# CRD.net
KiCad netlist of a schematic drawn in EAGLE
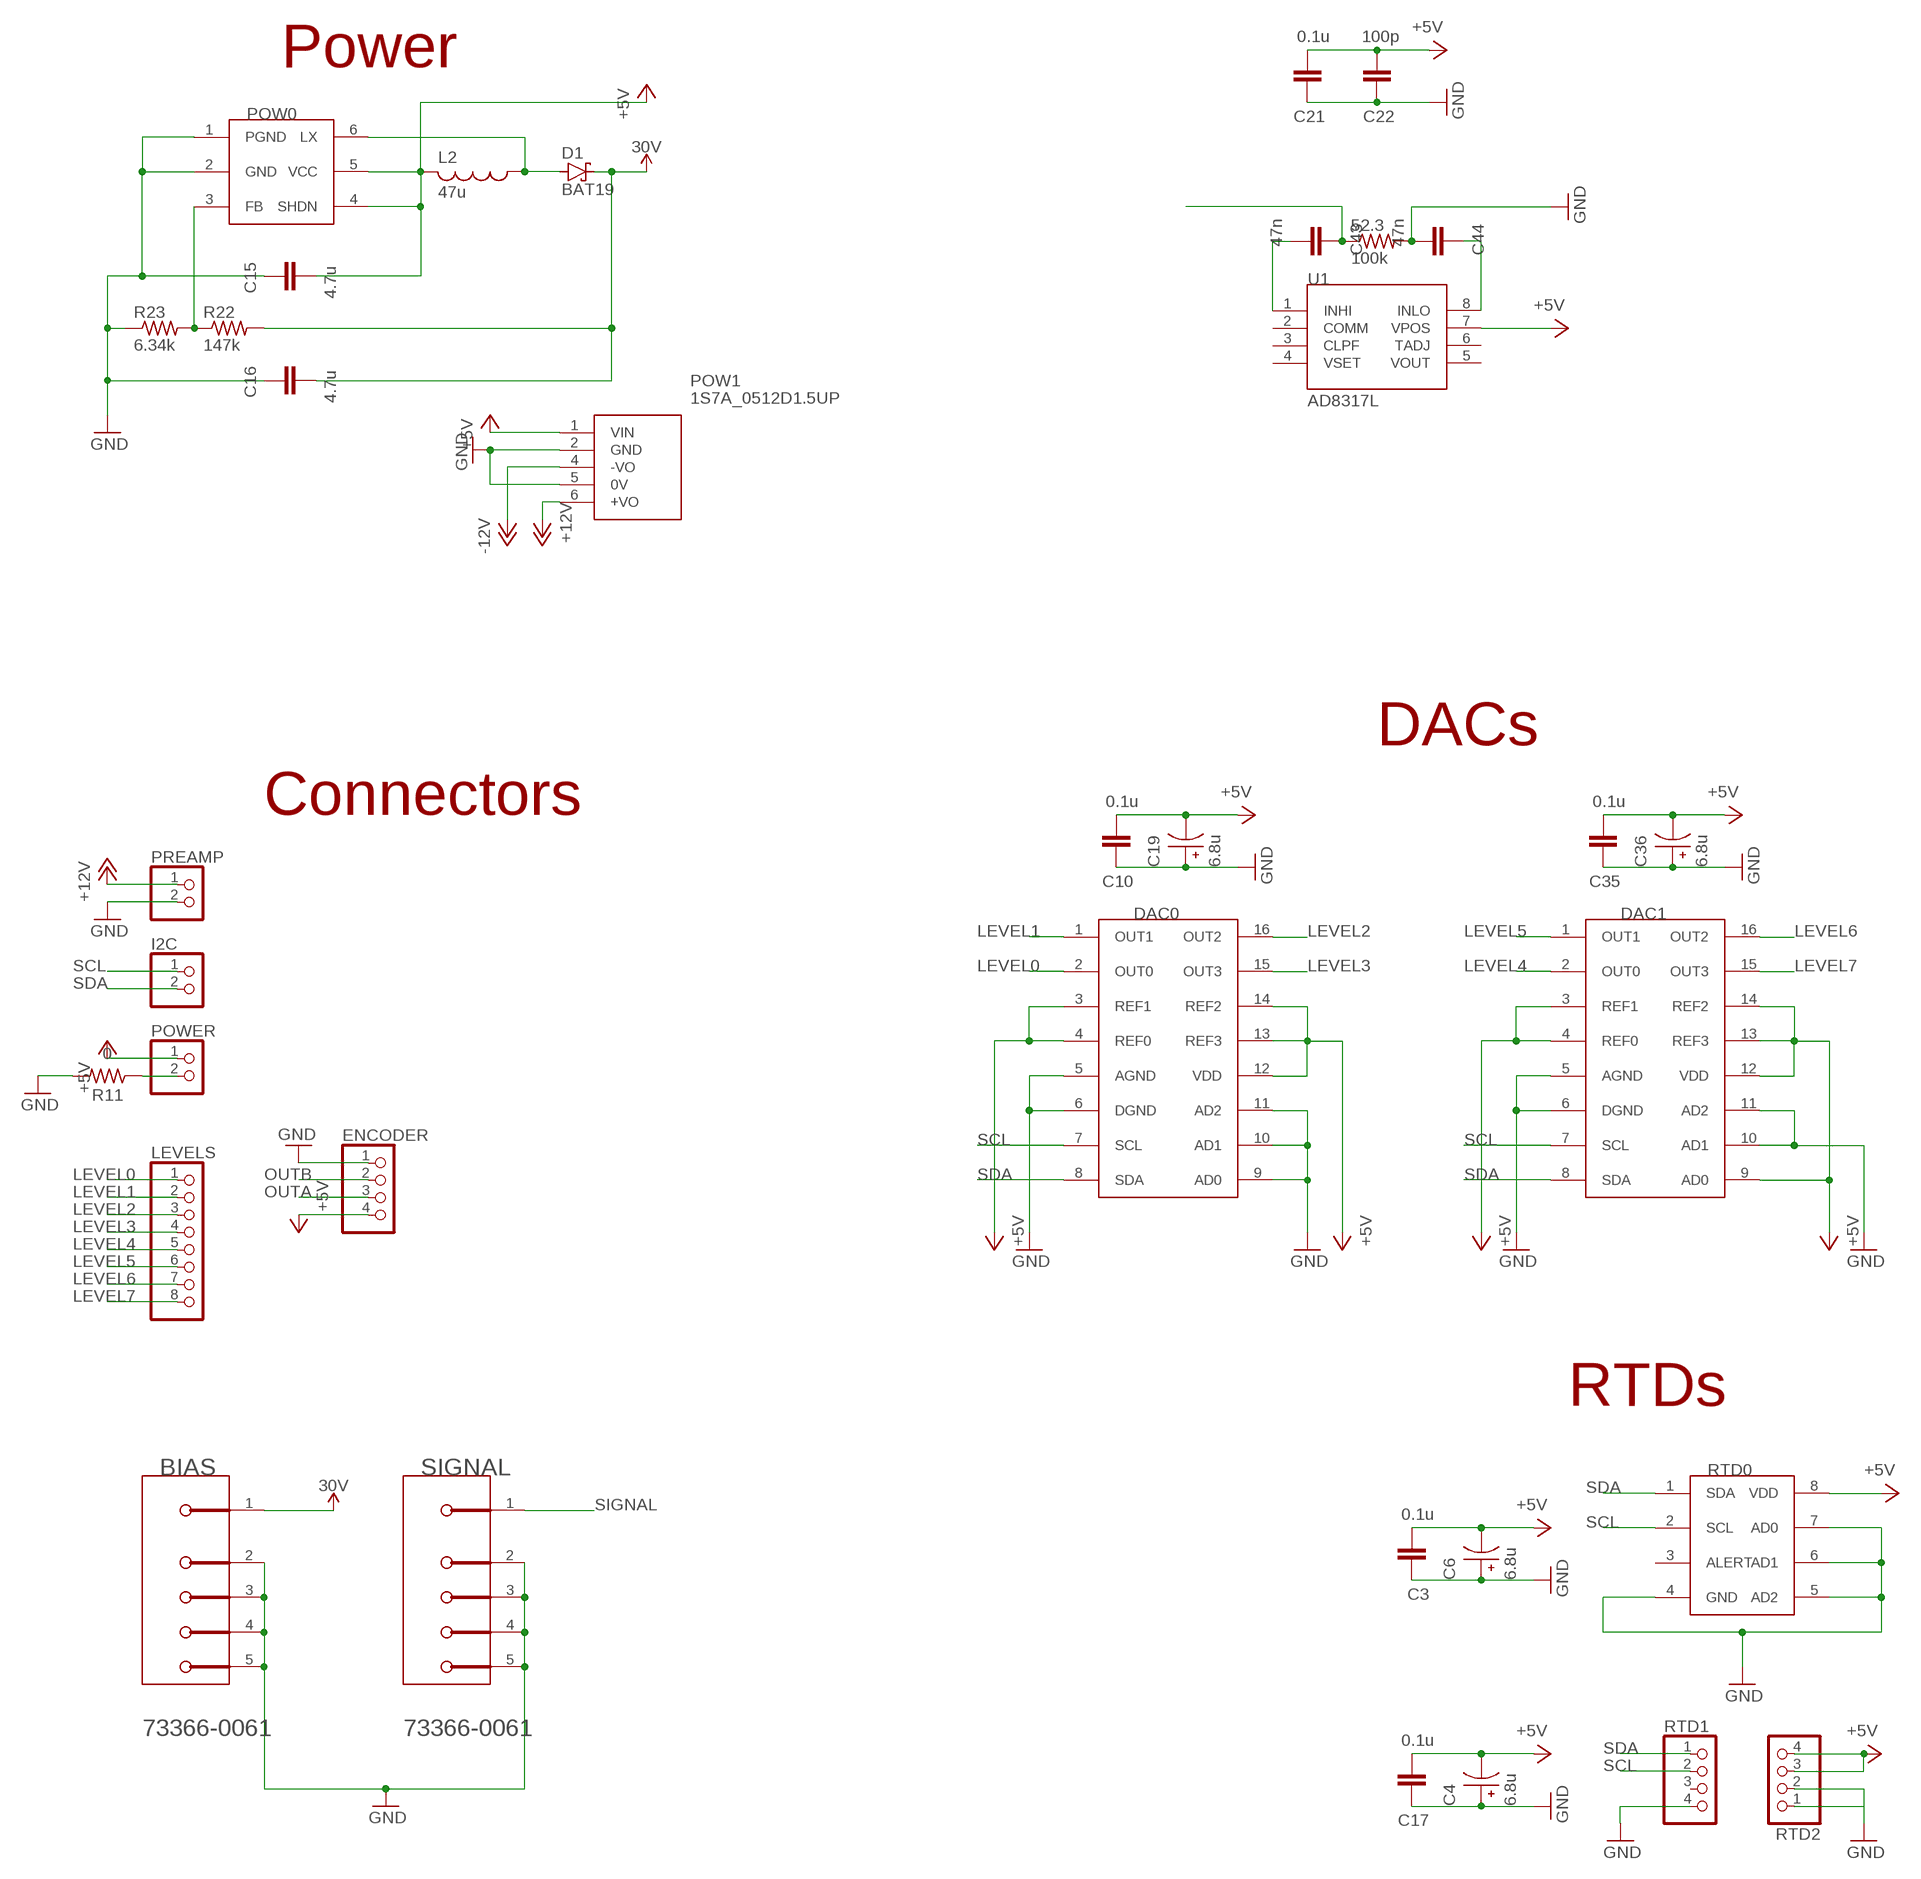
[diagram p0: schematic, sheet 1, part 1 of 2]
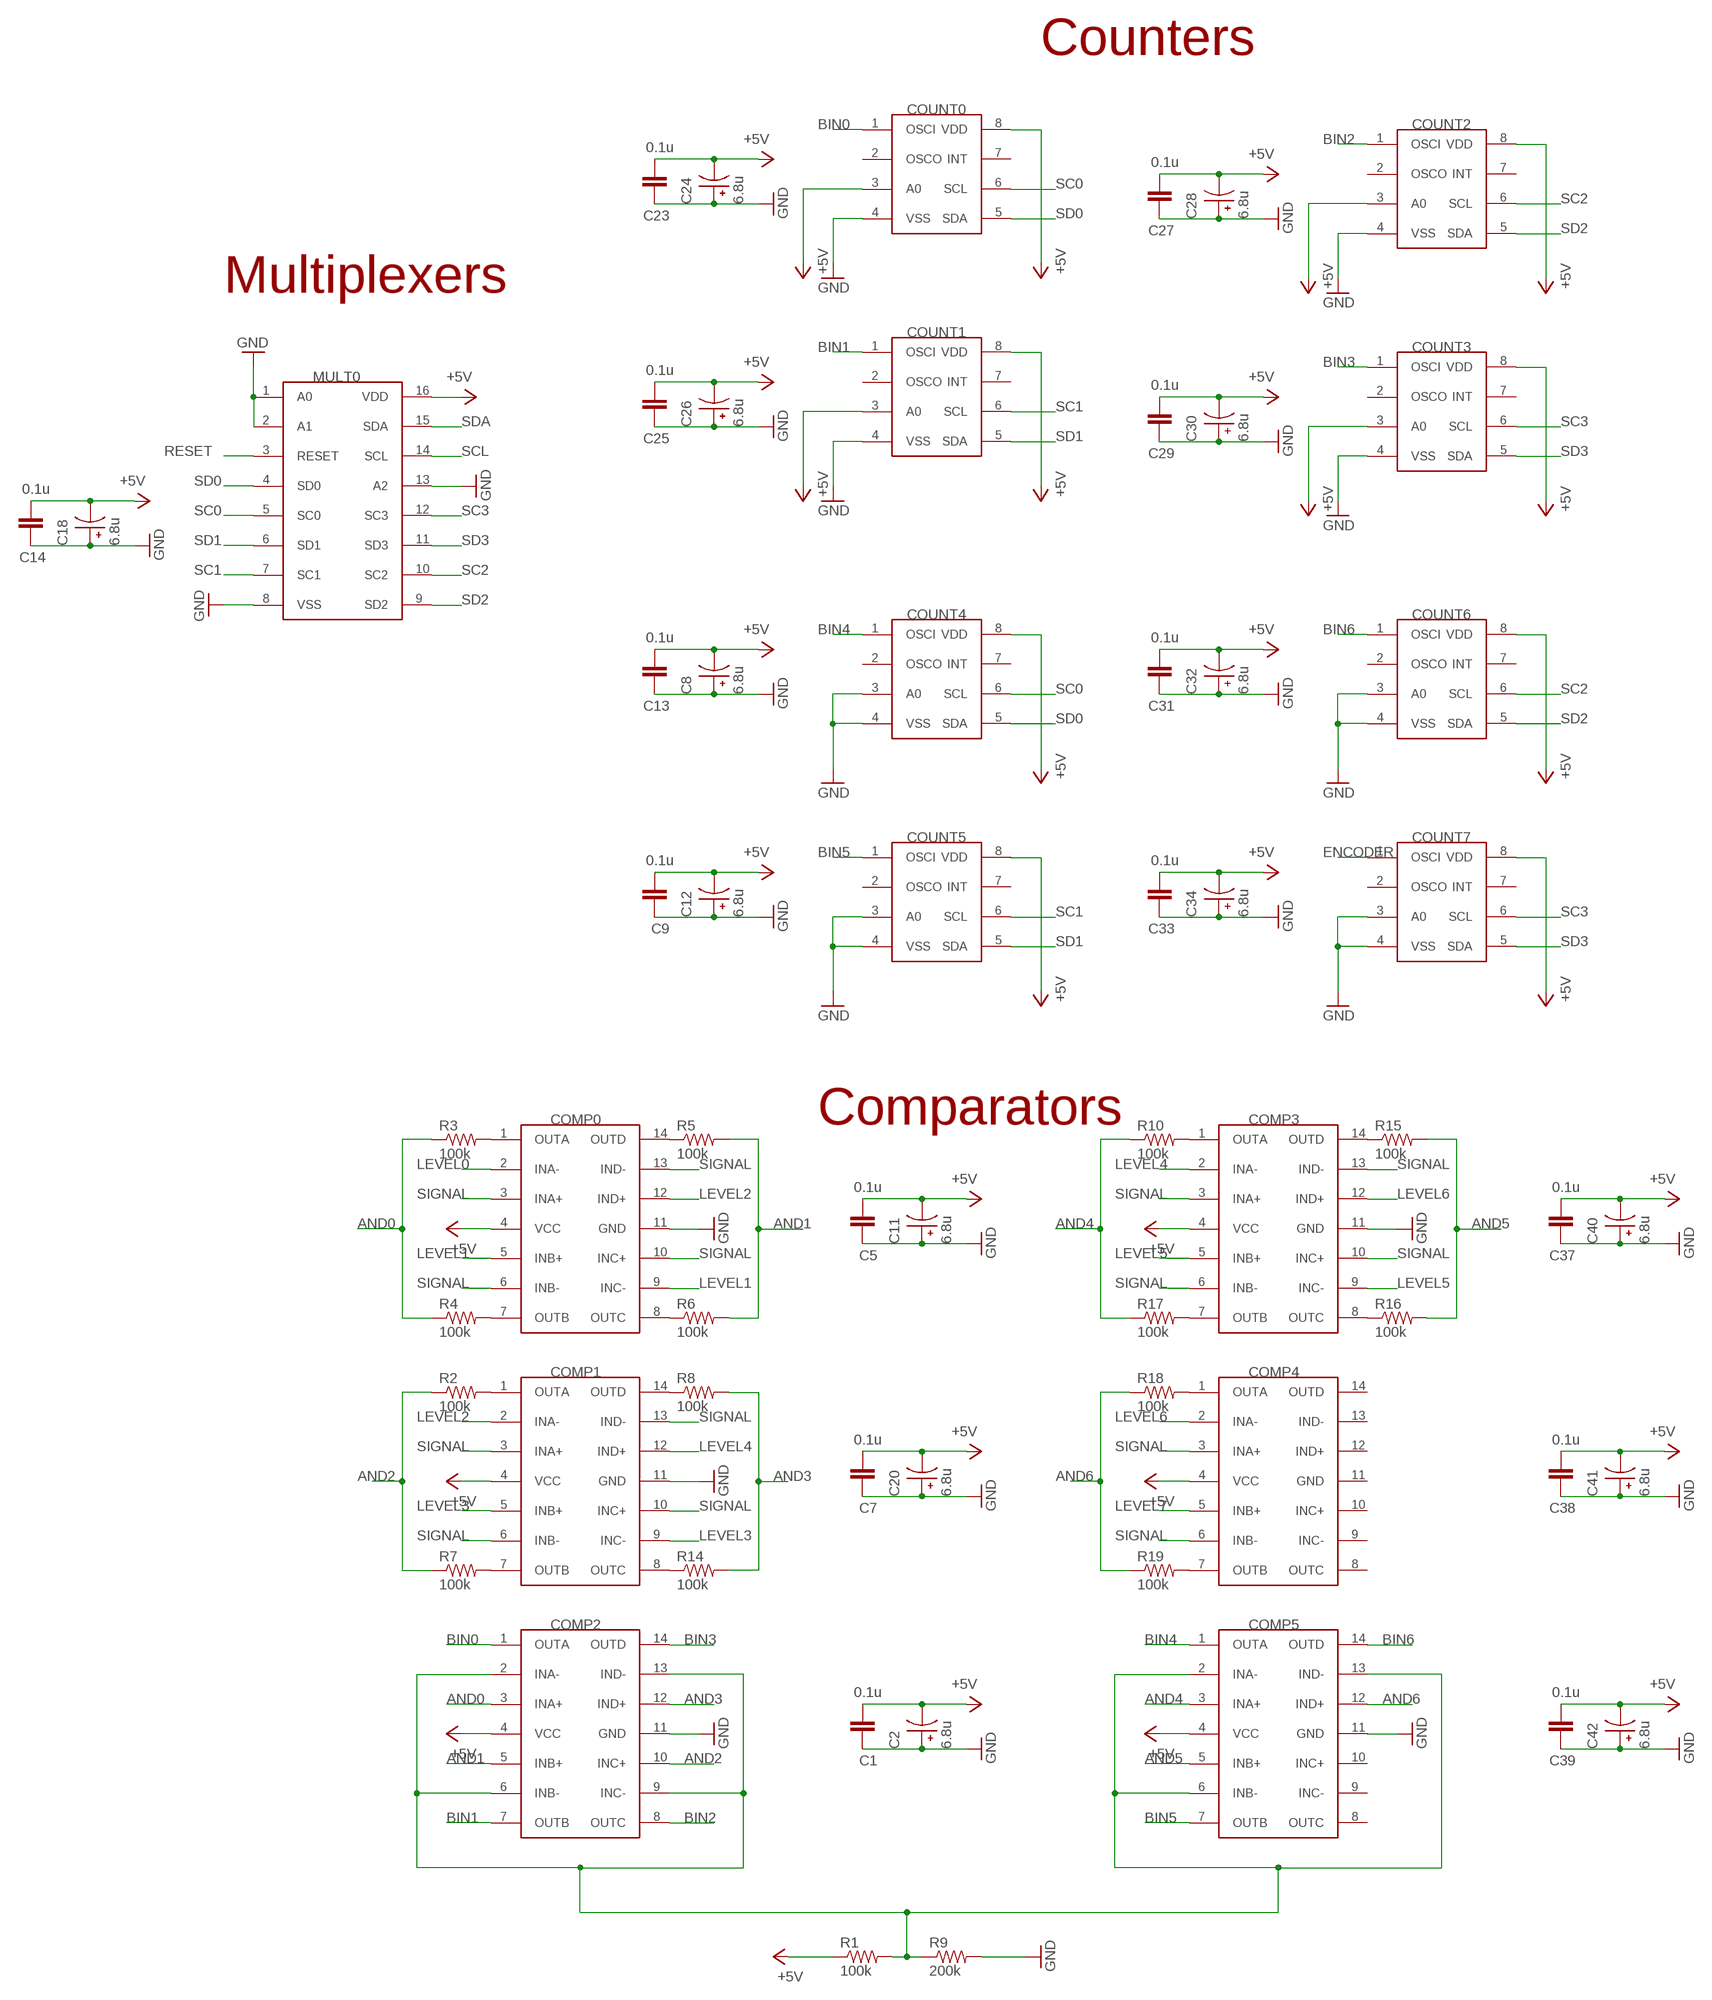
[diagram p1: schematic, sheet 1, part 2 of 2]

(export (version "E")
  (design (tool "Eeschema 10.0.6"))
  (components
    (comp (ref "52.3")
      (value "100k")
      (footprint "eagle-import:RES_1206")
      (fields
        (field (name "DIGIKEY_PART_NUMBER") "P0.0ETR-ND")
        (field (name "MANUFACTURER") "Panasonic Electronic Components")
        (field (name "MPN") "ERJ-8GEY0R00V")
        (field (name "CREATED_BY") "PCBLayout.com")
      )
      (libsource (lib "eagle-import") (part "ERJ-8GEY0R00V"))
    )
    (comp (ref "BIAS")
      (value "MOLEX_73366-0061MOLEX_73366-0061_0_0")
      (footprint "eagle-import:MOLEX_73366-0061_0")
      (fields
        (field (name "DIGIKEY_PART_NUMBER") "WM5541-ND")
        (field (name "MF") "Molex")
        (field (name "MOUSER_PART_NUMBER") "538-73366-0061")
      )
      (libsource (lib "eagle-import") (part "MOLEX_73366-0061MOLEX_73366-0061_0_0"))
    )
    (comp (ref "C1")
      (value "0.1u")
      (footprint "eagle-import:CAP_1206")
      (fields
        (field (name "DIGIKEY_PART_NUMBER") "GRM31CR60J107ME39L")
        (field (name "MANUFACTURER") "Murata Electronics North America")
        (field (name "CREATED_BY") "PCBLayout.com")
      )
      (libsource (lib "eagle-import") (part "GRM31CR60J107ME39L"))
    )
    (comp (ref "C2")
      (value "6.8u")
      (footprint "eagle-import:CAPPRD150W45D400H700")
      (fields
        (field (name "DIGI-KEY_PART_NUMBER") "P14493-ND")
        (field (name "MF") "Panasonic")
        (field (name "MP") "EEAGA1V6R8")
      )
      (libsource (lib "eagle-import") (part "EEAGA1V6R8"))
    )
    (comp (ref "C3")
      (value "0.1u")
      (footprint "eagle-import:CAP_1206")
      (fields
        (field (name "DIGIKEY_PART_NUMBER") "GRM31CR60J107ME39L")
        (field (name "MANUFACTURER") "Murata Electronics North America")
        (field (name "CREATED_BY") "PCBLayout.com")
      )
      (libsource (lib "eagle-import") (part "GRM31CR60J107ME39L"))
    )
    (comp (ref "C4")
      (value "6.8u")
      (footprint "eagle-import:CAPPRD150W45D400H700")
      (fields
        (field (name "DIGI-KEY_PART_NUMBER") "P14493-ND")
        (field (name "MF") "Panasonic")
        (field (name "MP") "EEAGA1V6R8")
      )
      (libsource (lib "eagle-import") (part "EEAGA1V6R8"))
    )
    (comp (ref "C5")
      (value "0.1u")
      (footprint "eagle-import:CAP_1206")
      (fields
        (field (name "DIGIKEY_PART_NUMBER") "GRM31CR60J107ME39L")
        (field (name "MANUFACTURER") "Murata Electronics North America")
        (field (name "CREATED_BY") "PCBLayout.com")
      )
      (libsource (lib "eagle-import") (part "GRM31CR60J107ME39L"))
    )
    (comp (ref "C6")
      (value "6.8u")
      (footprint "eagle-import:CAPPRD150W45D400H700")
      (fields
        (field (name "DIGI-KEY_PART_NUMBER") "P14493-ND")
        (field (name "MF") "Panasonic")
        (field (name "MP") "EEAGA1V6R8")
      )
      (libsource (lib "eagle-import") (part "EEAGA1V6R8"))
    )
    (comp (ref "C7")
      (value "0.1u")
      (footprint "eagle-import:CAP_1206")
      (fields
        (field (name "DIGIKEY_PART_NUMBER") "GRM31CR60J107ME39L")
        (field (name "MANUFACTURER") "Murata Electronics North America")
        (field (name "CREATED_BY") "PCBLayout.com")
      )
      (libsource (lib "eagle-import") (part "GRM31CR60J107ME39L"))
    )
    (comp (ref "C8")
      (value "6.8u")
      (footprint "eagle-import:CAPPRD150W45D400H700")
      (fields
        (field (name "DIGI-KEY_PART_NUMBER") "P14493-ND")
        (field (name "MF") "Panasonic")
        (field (name "MP") "EEAGA1V6R8")
      )
      (libsource (lib "eagle-import") (part "EEAGA1V6R8"))
    )
    (comp (ref "C9")
      (value "0.1u")
      (footprint "eagle-import:CAP_1206")
      (fields
        (field (name "DIGIKEY_PART_NUMBER") "GRM31CR60J107ME39L")
        (field (name "MANUFACTURER") "Murata Electronics North America")
        (field (name "CREATED_BY") "PCBLayout.com")
      )
      (libsource (lib "eagle-import") (part "GRM31CR60J107ME39L"))
    )
    (comp (ref "C10")
      (value "0.1u")
      (footprint "eagle-import:CAP_1206")
      (fields
        (field (name "DIGIKEY_PART_NUMBER") "GRM31CR60J107ME39L")
        (field (name "MANUFACTURER") "Murata Electronics North America")
        (field (name "CREATED_BY") "PCBLayout.com")
      )
      (libsource (lib "eagle-import") (part "GRM31CR60J107ME39L"))
    )
    (comp (ref "C11")
      (value "6.8u")
      (footprint "eagle-import:CAPPRD150W45D400H700")
      (fields
        (field (name "DIGI-KEY_PART_NUMBER") "P14493-ND")
        (field (name "MF") "Panasonic")
        (field (name "MP") "EEAGA1V6R8")
      )
      (libsource (lib "eagle-import") (part "EEAGA1V6R8"))
    )
    (comp (ref "C12")
      (value "6.8u")
      (footprint "eagle-import:CAPPRD150W45D400H700")
      (fields
        (field (name "DIGI-KEY_PART_NUMBER") "P14493-ND")
        (field (name "MF") "Panasonic")
        (field (name "MP") "EEAGA1V6R8")
      )
      (libsource (lib "eagle-import") (part "EEAGA1V6R8"))
    )
    (comp (ref "C13")
      (value "0.1u")
      (footprint "eagle-import:CAP_1206")
      (fields
        (field (name "DIGIKEY_PART_NUMBER") "GRM31CR60J107ME39L")
        (field (name "MANUFACTURER") "Murata Electronics North America")
        (field (name "CREATED_BY") "PCBLayout.com")
      )
      (libsource (lib "eagle-import") (part "GRM31CR60J107ME39L"))
    )
    (comp (ref "C14")
      (value "0.1u")
      (footprint "eagle-import:CAP_1206")
      (fields
        (field (name "DIGIKEY_PART_NUMBER") "GRM31CR60J107ME39L")
        (field (name "MANUFACTURER") "Murata Electronics North America")
        (field (name "CREATED_BY") "PCBLayout.com")
      )
      (libsource (lib "eagle-import") (part "GRM31CR60J107ME39L"))
    )
    (comp (ref "C15")
      (value "4.7u")
      (footprint "eagle-import:CAP_1206")
      (fields
        (field (name "DIGIKEY_PART_NUMBER") "GRM31CR60J107ME39L")
        (field (name "MANUFACTURER") "Murata Electronics North America")
        (field (name "CREATED_BY") "PCBLayout.com")
      )
      (libsource (lib "eagle-import") (part "GRM31CR60J107ME39L"))
    )
    (comp (ref "C16")
      (value "4.7u")
      (footprint "eagle-import:CAP_1206")
      (fields
        (field (name "DIGIKEY_PART_NUMBER") "GRM31CR60J107ME39L")
        (field (name "MANUFACTURER") "Murata Electronics North America")
        (field (name "CREATED_BY") "PCBLayout.com")
      )
      (libsource (lib "eagle-import") (part "GRM31CR60J107ME39L"))
    )
    (comp (ref "C17")
      (value "0.1u")
      (footprint "eagle-import:CAP_1206")
      (fields
        (field (name "DIGIKEY_PART_NUMBER") "GRM31CR60J107ME39L")
        (field (name "MANUFACTURER") "Murata Electronics North America")
        (field (name "CREATED_BY") "PCBLayout.com")
      )
      (libsource (lib "eagle-import") (part "GRM31CR60J107ME39L"))
    )
    (comp (ref "C18")
      (value "6.8u")
      (footprint "eagle-import:CAPPRD150W45D400H700")
      (fields
        (field (name "DIGI-KEY_PART_NUMBER") "P14493-ND")
        (field (name "MF") "Panasonic")
        (field (name "MP") "EEAGA1V6R8")
      )
      (libsource (lib "eagle-import") (part "EEAGA1V6R8"))
    )
    (comp (ref "C19")
      (value "6.8u")
      (footprint "eagle-import:CAPPRD150W45D400H700")
      (fields
        (field (name "DIGI-KEY_PART_NUMBER") "P14493-ND")
        (field (name "MF") "Panasonic")
        (field (name "MP") "EEAGA1V6R8")
      )
      (libsource (lib "eagle-import") (part "EEAGA1V6R8"))
    )
    (comp (ref "C20")
      (value "6.8u")
      (footprint "eagle-import:CAPPRD150W45D400H700")
      (fields
        (field (name "DIGI-KEY_PART_NUMBER") "P14493-ND")
        (field (name "MF") "Panasonic")
        (field (name "MP") "EEAGA1V6R8")
      )
      (libsource (lib "eagle-import") (part "EEAGA1V6R8"))
    )
    (comp (ref "C21")
      (value "0.1u")
      (footprint "eagle-import:CAP_1206")
      (fields
        (field (name "DIGIKEY_PART_NUMBER") "GRM31CR60J107ME39L")
        (field (name "MANUFACTURER") "Murata Electronics North America")
        (field (name "CREATED_BY") "PCBLayout.com")
      )
      (libsource (lib "eagle-import") (part "GRM31CR60J107ME39L"))
    )
    (comp (ref "C22")
      (value "100p")
      (footprint "eagle-import:CAP_1206")
      (fields
        (field (name "DIGIKEY_PART_NUMBER") "GRM31CR60J107ME39L")
        (field (name "MANUFACTURER") "Murata Electronics North America")
        (field (name "CREATED_BY") "PCBLayout.com")
      )
      (libsource (lib "eagle-import") (part "GRM31CR60J107ME39L"))
    )
    (comp (ref "C23")
      (value "0.1u")
      (footprint "eagle-import:CAP_1206")
      (fields
        (field (name "DIGIKEY_PART_NUMBER") "GRM31CR60J107ME39L")
        (field (name "MANUFACTURER") "Murata Electronics North America")
        (field (name "CREATED_BY") "PCBLayout.com")
      )
      (libsource (lib "eagle-import") (part "GRM31CR60J107ME39L"))
    )
    (comp (ref "C24")
      (value "6.8u")
      (footprint "eagle-import:CAPPRD150W45D400H700")
      (fields
        (field (name "DIGI-KEY_PART_NUMBER") "P14493-ND")
        (field (name "MF") "Panasonic")
        (field (name "MP") "EEAGA1V6R8")
      )
      (libsource (lib "eagle-import") (part "EEAGA1V6R8"))
    )
    (comp (ref "C25")
      (value "0.1u")
      (footprint "eagle-import:CAP_1206")
      (fields
        (field (name "DIGIKEY_PART_NUMBER") "GRM31CR60J107ME39L")
        (field (name "MANUFACTURER") "Murata Electronics North America")
        (field (name "CREATED_BY") "PCBLayout.com")
      )
      (libsource (lib "eagle-import") (part "GRM31CR60J107ME39L"))
    )
    (comp (ref "C26")
      (value "6.8u")
      (footprint "eagle-import:CAPPRD150W45D400H700")
      (fields
        (field (name "DIGI-KEY_PART_NUMBER") "P14493-ND")
        (field (name "MF") "Panasonic")
        (field (name "MP") "EEAGA1V6R8")
      )
      (libsource (lib "eagle-import") (part "EEAGA1V6R8"))
    )
    (comp (ref "C27")
      (value "0.1u")
      (footprint "eagle-import:CAP_1206")
      (fields
        (field (name "DIGIKEY_PART_NUMBER") "GRM31CR60J107ME39L")
        (field (name "MANUFACTURER") "Murata Electronics North America")
        (field (name "CREATED_BY") "PCBLayout.com")
      )
      (libsource (lib "eagle-import") (part "GRM31CR60J107ME39L"))
    )
    (comp (ref "C28")
      (value "6.8u")
      (footprint "eagle-import:CAPPRD150W45D400H700")
      (fields
        (field (name "DIGI-KEY_PART_NUMBER") "P14493-ND")
        (field (name "MF") "Panasonic")
        (field (name "MP") "EEAGA1V6R8")
      )
      (libsource (lib "eagle-import") (part "EEAGA1V6R8"))
    )
    (comp (ref "C29")
      (value "0.1u")
      (footprint "eagle-import:CAP_1206")
      (fields
        (field (name "DIGIKEY_PART_NUMBER") "GRM31CR60J107ME39L")
        (field (name "MANUFACTURER") "Murata Electronics North America")
        (field (name "CREATED_BY") "PCBLayout.com")
      )
      (libsource (lib "eagle-import") (part "GRM31CR60J107ME39L"))
    )
    (comp (ref "C30")
      (value "6.8u")
      (footprint "eagle-import:CAPPRD150W45D400H700")
      (fields
        (field (name "DIGI-KEY_PART_NUMBER") "P14493-ND")
        (field (name "MF") "Panasonic")
        (field (name "MP") "EEAGA1V6R8")
      )
      (libsource (lib "eagle-import") (part "EEAGA1V6R8"))
    )
    (comp (ref "C31")
      (value "0.1u")
      (footprint "eagle-import:CAP_1206")
      (fields
        (field (name "DIGIKEY_PART_NUMBER") "GRM31CR60J107ME39L")
        (field (name "MANUFACTURER") "Murata Electronics North America")
        (field (name "CREATED_BY") "PCBLayout.com")
      )
      (libsource (lib "eagle-import") (part "GRM31CR60J107ME39L"))
    )
    (comp (ref "C32")
      (value "6.8u")
      (footprint "eagle-import:CAPPRD150W45D400H700")
      (fields
        (field (name "DIGI-KEY_PART_NUMBER") "P14493-ND")
        (field (name "MF") "Panasonic")
        (field (name "MP") "EEAGA1V6R8")
      )
      (libsource (lib "eagle-import") (part "EEAGA1V6R8"))
    )
    (comp (ref "C33")
      (value "0.1u")
      (footprint "eagle-import:CAP_1206")
      (fields
        (field (name "DIGIKEY_PART_NUMBER") "GRM31CR60J107ME39L")
        (field (name "MANUFACTURER") "Murata Electronics North America")
        (field (name "CREATED_BY") "PCBLayout.com")
      )
      (libsource (lib "eagle-import") (part "GRM31CR60J107ME39L"))
    )
    (comp (ref "C34")
      (value "6.8u")
      (footprint "eagle-import:CAPPRD150W45D400H700")
      (fields
        (field (name "DIGI-KEY_PART_NUMBER") "P14493-ND")
        (field (name "MF") "Panasonic")
        (field (name "MP") "EEAGA1V6R8")
      )
      (libsource (lib "eagle-import") (part "EEAGA1V6R8"))
    )
    (comp (ref "C35")
      (value "0.1u")
      (footprint "eagle-import:CAP_1206")
      (fields
        (field (name "DIGIKEY_PART_NUMBER") "GRM31CR60J107ME39L")
        (field (name "MANUFACTURER") "Murata Electronics North America")
        (field (name "CREATED_BY") "PCBLayout.com")
      )
      (libsource (lib "eagle-import") (part "GRM31CR60J107ME39L"))
    )
    (comp (ref "C36")
      (value "6.8u")
      (footprint "eagle-import:CAPPRD150W45D400H700")
      (fields
        (field (name "DIGI-KEY_PART_NUMBER") "P14493-ND")
        (field (name "MF") "Panasonic")
        (field (name "MP") "EEAGA1V6R8")
      )
      (libsource (lib "eagle-import") (part "EEAGA1V6R8"))
    )
    (comp (ref "C37")
      (value "0.1u")
      (footprint "eagle-import:CAP_1206")
      (fields
        (field (name "DIGIKEY_PART_NUMBER") "GRM31CR60J107ME39L")
        (field (name "MANUFACTURER") "Murata Electronics North America")
        (field (name "CREATED_BY") "PCBLayout.com")
      )
      (libsource (lib "eagle-import") (part "GRM31CR60J107ME39L"))
    )
    (comp (ref "C38")
      (value "0.1u")
      (footprint "eagle-import:CAP_1206")
      (fields
        (field (name "DIGIKEY_PART_NUMBER") "GRM31CR60J107ME39L")
        (field (name "MANUFACTURER") "Murata Electronics North America")
        (field (name "CREATED_BY") "PCBLayout.com")
      )
      (libsource (lib "eagle-import") (part "GRM31CR60J107ME39L"))
    )
    (comp (ref "C39")
      (value "0.1u")
      (footprint "eagle-import:CAP_1206")
      (fields
        (field (name "DIGIKEY_PART_NUMBER") "GRM31CR60J107ME39L")
        (field (name "MANUFACTURER") "Murata Electronics North America")
        (field (name "CREATED_BY") "PCBLayout.com")
      )
      (libsource (lib "eagle-import") (part "GRM31CR60J107ME39L"))
    )
    (comp (ref "C40")
      (value "6.8u")
      (footprint "eagle-import:CAPPRD150W45D400H700")
      (fields
        (field (name "DIGI-KEY_PART_NUMBER") "P14493-ND")
        (field (name "MF") "Panasonic")
        (field (name "MP") "EEAGA1V6R8")
      )
      (libsource (lib "eagle-import") (part "EEAGA1V6R8"))
    )
    (comp (ref "C41")
      (value "6.8u")
      (footprint "eagle-import:CAPPRD150W45D400H700")
      (fields
        (field (name "DIGI-KEY_PART_NUMBER") "P14493-ND")
        (field (name "MF") "Panasonic")
        (field (name "MP") "EEAGA1V6R8")
      )
      (libsource (lib "eagle-import") (part "EEAGA1V6R8"))
    )
    (comp (ref "C42")
      (value "6.8u")
      (footprint "eagle-import:CAPPRD150W45D400H700")
      (fields
        (field (name "DIGI-KEY_PART_NUMBER") "P14493-ND")
        (field (name "MF") "Panasonic")
        (field (name "MP") "EEAGA1V6R8")
      )
      (libsource (lib "eagle-import") (part "EEAGA1V6R8"))
    )
    (comp (ref "C43")
      (value "47n")
      (footprint "eagle-import:CAP_1206")
      (fields
        (field (name "DIGIKEY_PART_NUMBER") "GRM31CR60J107ME39L")
        (field (name "MANUFACTURER") "Murata Electronics North America")
        (field (name "CREATED_BY") "PCBLayout.com")
      )
      (libsource (lib "eagle-import") (part "GRM31CR60J107ME39L"))
    )
    (comp (ref "C44")
      (value "47n")
      (footprint "eagle-import:CAP_1206")
      (fields
        (field (name "DIGIKEY_PART_NUMBER") "GRM31CR60J107ME39L")
        (field (name "MANUFACTURER") "Murata Electronics North America")
        (field (name "CREATED_BY") "PCBLayout.com")
      )
      (libsource (lib "eagle-import") (part "GRM31CR60J107ME39L"))
    )
    (comp (ref "COMP0")
      (value "MAX9108ESD+")
      (footprint "eagle-import:SOIC127P600X155-14N")
      (libsource (lib "eagle-import") (part "MAX9108ESD+"))
    )
    (comp (ref "COMP1")
      (value "MAX9108ESD+")
      (footprint "eagle-import:SOIC127P600X155-14N")
      (libsource (lib "eagle-import") (part "MAX9108ESD+"))
    )
    (comp (ref "COMP2")
      (value "MAX9108ESD+")
      (footprint "eagle-import:SOIC127P600X155-14N")
      (libsource (lib "eagle-import") (part "MAX9108ESD+"))
    )
    (comp (ref "COMP3")
      (value "MAX9108ESD+")
      (footprint "eagle-import:SOIC127P600X155-14N")
      (libsource (lib "eagle-import") (part "MAX9108ESD+"))
    )
    (comp (ref "COMP4")
      (value "MAX9108ESD+")
      (footprint "eagle-import:SOIC127P600X155-14N")
      (libsource (lib "eagle-import") (part "MAX9108ESD+"))
    )
    (comp (ref "COMP5")
      (value "MAX9108ESD+")
      (footprint "eagle-import:SOIC127P600X155-14N")
      (libsource (lib "eagle-import") (part "MAX9108ESD+"))
    )
    (comp (ref "COUNT0")
      (value "PCF8583")
      (footprint "eagle-import:SOIC127P1032X265-8N")
      (libsource (lib "eagle-import") (part "PCF8583"))
    )
    (comp (ref "COUNT1")
      (value "PCF8583")
      (footprint "eagle-import:SOIC127P1032X265-8N")
      (libsource (lib "eagle-import") (part "PCF8583"))
    )
    (comp (ref "COUNT2")
      (value "PCF8583")
      (footprint "eagle-import:SOIC127P1032X265-8N")
      (libsource (lib "eagle-import") (part "PCF8583"))
    )
    (comp (ref "COUNT3")
      (value "PCF8583")
      (footprint "eagle-import:SOIC127P1032X265-8N")
      (libsource (lib "eagle-import") (part "PCF8583"))
    )
    (comp (ref "COUNT4")
      (value "PCF8583")
      (footprint "eagle-import:SOIC127P1032X265-8N")
      (libsource (lib "eagle-import") (part "PCF8583"))
    )
    (comp (ref "COUNT5")
      (value "PCF8583")
      (footprint "eagle-import:SOIC127P1032X265-8N")
      (libsource (lib "eagle-import") (part "PCF8583"))
    )
    (comp (ref "COUNT6")
      (value "PCF8583")
      (footprint "eagle-import:SOIC127P1032X265-8N")
      (libsource (lib "eagle-import") (part "PCF8583"))
    )
    (comp (ref "COUNT7")
      (value "PCF8583")
      (footprint "eagle-import:SOIC127P1032X265-8N")
      (libsource (lib "eagle-import") (part "PCF8583"))
    )
    (comp (ref "D1")
      (value "BAT19")
      (footprint "eagle-import:DO35-10")
      (libsource (lib "eagle-import") (part "BAT19"))
    )
    (comp (ref "DAC0")
      (value "MAX520BEWE+")
      (footprint "eagle-import:SOIC127P1032X265-16N")
      (libsource (lib "eagle-import") (part "MAX520BEWE+"))
    )
    (comp (ref "DAC1")
      (value "MAX520BEWE+")
      (footprint "eagle-import:SOIC127P1032X265-16N")
      (libsource (lib "eagle-import") (part "MAX520BEWE+"))
    )
    (comp (ref "ENCODER")
      (value "PINHD-1X4")
      (footprint "eagle-import:1X04")
      (libsource (lib "eagle-import") (part "PINHD-1X4"))
    )
    (comp (ref "I2C")
      (value "PINHD-1X2")
      (footprint "eagle-import:1X02")
      (libsource (lib "eagle-import") (part "PINHD-1X2"))
    )
    (comp (ref "L2")
      (value "47u")
      (footprint "eagle-import:L1812")
      (libsource (lib "eagle-import") (part "L-USL1812"))
    )
    (comp (ref "LEVELS")
      (value "PINHD-1X8")
      (footprint "eagle-import:1X08")
      (libsource (lib "eagle-import") (part "PINHD-1X8"))
    )
    (comp (ref "MULT0")
      (value "PCA9546A")
      (footprint "eagle-import:SOIC127P600X175-16N")
      (libsource (lib "eagle-import") (part "PCA9546A"))
    )
    (comp (ref "POW0")
      (value "MAX5025")
      (footprint "eagle-import:SOT95P240X110-6N")
      (libsource (lib "eagle-import") (part "MAX5025"))
    )
    (comp (ref "POW1")
      (value "1S7A_0512D1.5UP")
      (footprint "eagle-import:1S7A_0505D15UP")
      (libsource (lib "eagle-import") (part "1S7A_0512D1.5UP"))
    )
    (comp (ref "POWER")
      (value "PINHD-1X2")
      (footprint "eagle-import:1X02")
      (libsource (lib "eagle-import") (part "PINHD-1X2"))
    )
    (comp (ref "PREAMP")
      (value "PINHD-1X2")
      (footprint "eagle-import:1X02")
      (libsource (lib "eagle-import") (part "PINHD-1X2"))
    )
    (comp (ref "R1")
      (value "100k")
      (footprint "eagle-import:RES_1206")
      (fields
        (field (name "DIGIKEY_PART_NUMBER") "P0.0ETR-ND")
        (field (name "MANUFACTURER") "Panasonic Electronic Components")
        (field (name "MPN") "ERJ-8GEY0R00V")
        (field (name "CREATED_BY") "PCBLayout.com")
      )
      (libsource (lib "eagle-import") (part "ERJ-8GEY0R00V"))
    )
    (comp (ref "R2")
      (value "100k")
      (footprint "eagle-import:RES_1206")
      (fields
        (field (name "DIGIKEY_PART_NUMBER") "P0.0ETR-ND")
        (field (name "MANUFACTURER") "Panasonic Electronic Components")
        (field (name "MPN") "ERJ-8GEY0R00V")
        (field (name "CREATED_BY") "PCBLayout.com")
      )
      (libsource (lib "eagle-import") (part "ERJ-8GEY0R00V"))
    )
    (comp (ref "R3")
      (value "100k")
      (footprint "eagle-import:RES_1206")
      (fields
        (field (name "DIGIKEY_PART_NUMBER") "P0.0ETR-ND")
        (field (name "MANUFACTURER") "Panasonic Electronic Components")
        (field (name "MPN") "ERJ-8GEY0R00V")
        (field (name "CREATED_BY") "PCBLayout.com")
      )
      (libsource (lib "eagle-import") (part "ERJ-8GEY0R00V"))
    )
    (comp (ref "R4")
      (value "100k")
      (footprint "eagle-import:RES_1206")
      (fields
        (field (name "DIGIKEY_PART_NUMBER") "P0.0ETR-ND")
        (field (name "MANUFACTURER") "Panasonic Electronic Components")
        (field (name "MPN") "ERJ-8GEY0R00V")
        (field (name "CREATED_BY") "PCBLayout.com")
      )
      (libsource (lib "eagle-import") (part "ERJ-8GEY0R00V"))
    )
    (comp (ref "R5")
      (value "100k")
      (footprint "eagle-import:RES_1206")
      (fields
        (field (name "DIGIKEY_PART_NUMBER") "P0.0ETR-ND")
        (field (name "MANUFACTURER") "Panasonic Electronic Components")
        (field (name "MPN") "ERJ-8GEY0R00V")
        (field (name "CREATED_BY") "PCBLayout.com")
      )
      (libsource (lib "eagle-import") (part "ERJ-8GEY0R00V"))
    )
    (comp (ref "R6")
      (value "100k")
      (footprint "eagle-import:RES_1206")
      (fields
        (field (name "DIGIKEY_PART_NUMBER") "P0.0ETR-ND")
        (field (name "MANUFACTURER") "Panasonic Electronic Components")
        (field (name "MPN") "ERJ-8GEY0R00V")
        (field (name "CREATED_BY") "PCBLayout.com")
      )
      (libsource (lib "eagle-import") (part "ERJ-8GEY0R00V"))
    )
    (comp (ref "R7")
      (value "100k")
      (footprint "eagle-import:RES_1206")
      (fields
        (field (name "DIGIKEY_PART_NUMBER") "P0.0ETR-ND")
        (field (name "MANUFACTURER") "Panasonic Electronic Components")
        (field (name "MPN") "ERJ-8GEY0R00V")
        (field (name "CREATED_BY") "PCBLayout.com")
      )
      (libsource (lib "eagle-import") (part "ERJ-8GEY0R00V"))
    )
    (comp (ref "R8")
      (value "100k")
      (footprint "eagle-import:RES_1206")
      (fields
        (field (name "DIGIKEY_PART_NUMBER") "P0.0ETR-ND")
        (field (name "MANUFACTURER") "Panasonic Electronic Components")
        (field (name "MPN") "ERJ-8GEY0R00V")
        (field (name "CREATED_BY") "PCBLayout.com")
      )
      (libsource (lib "eagle-import") (part "ERJ-8GEY0R00V"))
    )
    (comp (ref "R9")
      (value "200k")
      (footprint "eagle-import:RES_1206")
      (fields
        (field (name "DIGIKEY_PART_NUMBER") "P0.0ETR-ND")
        (field (name "MANUFACTURER") "Panasonic Electronic Components")
        (field (name "MPN") "ERJ-8GEY0R00V")
        (field (name "CREATED_BY") "PCBLayout.com")
      )
      (libsource (lib "eagle-import") (part "ERJ-8GEY0R00V"))
    )
    (comp (ref "R10")
      (value "100k")
      (footprint "eagle-import:RES_1206")
      (fields
        (field (name "DIGIKEY_PART_NUMBER") "P0.0ETR-ND")
        (field (name "MANUFACTURER") "Panasonic Electronic Components")
        (field (name "MPN") "ERJ-8GEY0R00V")
        (field (name "CREATED_BY") "PCBLayout.com")
      )
      (libsource (lib "eagle-import") (part "ERJ-8GEY0R00V"))
    )
    (comp (ref "R11")
      (value "0")
      (footprint "eagle-import:RESAD724W46L381D178B")
      (libsource (lib "eagle-import") (part "R-USAXIAL-7.2MM-PITCH_"))
    )
    (comp (ref "R14")
      (value "100k")
      (footprint "eagle-import:RES_1206")
      (fields
        (field (name "DIGIKEY_PART_NUMBER") "P0.0ETR-ND")
        (field (name "MANUFACTURER") "Panasonic Electronic Components")
        (field (name "MPN") "ERJ-8GEY0R00V")
        (field (name "CREATED_BY") "PCBLayout.com")
      )
      (libsource (lib "eagle-import") (part "ERJ-8GEY0R00V"))
    )
    (comp (ref "R15")
      (value "100k")
      (footprint "eagle-import:RES_1206")
      (fields
        (field (name "DIGIKEY_PART_NUMBER") "P0.0ETR-ND")
        (field (name "MANUFACTURER") "Panasonic Electronic Components")
        (field (name "MPN") "ERJ-8GEY0R00V")
        (field (name "CREATED_BY") "PCBLayout.com")
      )
      (libsource (lib "eagle-import") (part "ERJ-8GEY0R00V"))
    )
    (comp (ref "R16")
      (value "100k")
      (footprint "eagle-import:RES_1206")
      (fields
        (field (name "DIGIKEY_PART_NUMBER") "P0.0ETR-ND")
        (field (name "MANUFACTURER") "Panasonic Electronic Components")
        (field (name "MPN") "ERJ-8GEY0R00V")
        (field (name "CREATED_BY") "PCBLayout.com")
      )
      (libsource (lib "eagle-import") (part "ERJ-8GEY0R00V"))
    )
    (comp (ref "R17")
      (value "100k")
      (footprint "eagle-import:RES_1206")
      (fields
        (field (name "DIGIKEY_PART_NUMBER") "P0.0ETR-ND")
        (field (name "MANUFACTURER") "Panasonic Electronic Components")
        (field (name "MPN") "ERJ-8GEY0R00V")
        (field (name "CREATED_BY") "PCBLayout.com")
      )
      (libsource (lib "eagle-import") (part "ERJ-8GEY0R00V"))
    )
    (comp (ref "R18")
      (value "100k")
      (footprint "eagle-import:RES_1206")
      (fields
        (field (name "DIGIKEY_PART_NUMBER") "P0.0ETR-ND")
        (field (name "MANUFACTURER") "Panasonic Electronic Components")
        (field (name "MPN") "ERJ-8GEY0R00V")
        (field (name "CREATED_BY") "PCBLayout.com")
      )
      (libsource (lib "eagle-import") (part "ERJ-8GEY0R00V"))
    )
    (comp (ref "R19")
      (value "100k")
      (footprint "eagle-import:RES_1206")
      (fields
        (field (name "DIGIKEY_PART_NUMBER") "P0.0ETR-ND")
        (field (name "MANUFACTURER") "Panasonic Electronic Components")
        (field (name "MPN") "ERJ-8GEY0R00V")
        (field (name "CREATED_BY") "PCBLayout.com")
      )
      (libsource (lib "eagle-import") (part "ERJ-8GEY0R00V"))
    )
    (comp (ref "R22")
      (value "147k")
      (footprint "eagle-import:RES_1206")
      (fields
        (field (name "DIGIKEY_PART_NUMBER") "P0.0ETR-ND")
        (field (name "MANUFACTURER") "Panasonic Electronic Components")
        (field (name "MPN") "ERJ-8GEY0R00V")
        (field (name "CREATED_BY") "PCBLayout.com")
      )
      (libsource (lib "eagle-import") (part "ERJ-8GEY0R00V"))
    )
    (comp (ref "R23")
      (value "6.34k")
      (footprint "eagle-import:RES_1206")
      (fields
        (field (name "DIGIKEY_PART_NUMBER") "P0.0ETR-ND")
        (field (name "MANUFACTURER") "Panasonic Electronic Components")
        (field (name "MPN") "ERJ-8GEY0R00V")
        (field (name "CREATED_BY") "PCBLayout.com")
      )
      (libsource (lib "eagle-import") (part "ERJ-8GEY0R00V"))
    )
    (comp (ref "RTD0")
      (value "NCT175DMR2G")
      (footprint "eagle-import:SOP65P490X110-8N")
      (libsource (lib "eagle-import") (part "NCT175DMR2G"))
    )
    (comp (ref "RTD1")
      (value "PINHD-1X4")
      (footprint "eagle-import:1X04")
      (libsource (lib "eagle-import") (part "PINHD-1X4"))
    )
    (comp (ref "RTD2")
      (value "PINHD-1X4")
      (footprint "eagle-import:1X04")
      (libsource (lib "eagle-import") (part "PINHD-1X4"))
    )
    (comp (ref "SIGNAL")
      (value "MOLEX_73366-0061MOLEX_73366-0061_0_0")
      (footprint "eagle-import:MOLEX_73366-0061_0")
      (fields
        (field (name "DIGIKEY_PART_NUMBER") "WM5541-ND")
        (field (name "MF") "Molex")
        (field (name "MOUSER_PART_NUMBER") "538-73366-0061")
      )
      (libsource (lib "eagle-import") (part "MOLEX_73366-0061MOLEX_73366-0061_0_0"))
    )
    (comp (ref "U1")
      (value "AD8317L")
      (footprint "eagle-import:DFN-8-EXTRA")
      (fields (field (name "MF") "Analog Devices") (field (name "MP") "AD8317"))
      (libsource (lib "eagle-import") (part "AD8317L"))
    )
  )
  (nets
    (net (code "1") (name "+5V") (class "Default")
      (node (ref "C1") (pin "2") (pinfunction "2_2") (pintype "passive"))
      (node (ref "C10") (pin "2") (pinfunction "2_2") (pintype "passive"))
      (node (ref "C11") (pin "N") (pinfunction "N_N") (pintype "passive"))
      (node (ref "C12") (pin "N") (pinfunction "N_N") (pintype "passive"))
      (node (ref "C13") (pin "2") (pinfunction "2_2") (pintype "passive"))
      (node (ref "C14") (pin "2") (pinfunction "2_2") (pintype "passive"))
      (node (ref "C15") (pin "2") (pinfunction "2_2") (pintype "passive"))
      (node (ref "C17") (pin "2") (pinfunction "2_2") (pintype "passive"))
      (node (ref "C18") (pin "N") (pinfunction "N_N") (pintype "passive"))
      (node (ref "C19") (pin "N") (pinfunction "N_N") (pintype "passive"))
      (node (ref "C2") (pin "N") (pinfunction "N_N") (pintype "passive"))
      (node (ref "C20") (pin "N") (pinfunction "N_N") (pintype "passive"))
      (node (ref "C21") (pin "2") (pinfunction "2_2") (pintype "passive"))
      (node (ref "C22") (pin "2") (pinfunction "2_2") (pintype "passive"))
      (node (ref "C23") (pin "2") (pinfunction "2_2") (pintype "passive"))
      (node (ref "C24") (pin "N") (pinfunction "N_N") (pintype "passive"))
      (node (ref "C25") (pin "2") (pinfunction "2_2") (pintype "passive"))
      (node (ref "C26") (pin "N") (pinfunction "N_N") (pintype "passive"))
      (node (ref "C27") (pin "2") (pinfunction "2_2") (pintype "passive"))
      (node (ref "C28") (pin "N") (pinfunction "N_N") (pintype "passive"))
      (node (ref "C29") (pin "2") (pinfunction "2_2") (pintype "passive"))
      (node (ref "C3") (pin "2") (pinfunction "2_2") (pintype "passive"))
      (node (ref "C30") (pin "N") (pinfunction "N_N") (pintype "passive"))
      (node (ref "C31") (pin "2") (pinfunction "2_2") (pintype "passive"))
      (node (ref "C32") (pin "N") (pinfunction "N_N") (pintype "passive"))
      (node (ref "C33") (pin "2") (pinfunction "2_2") (pintype "passive"))
      (node (ref "C34") (pin "N") (pinfunction "N_N") (pintype "passive"))
      (node (ref "C35") (pin "2") (pinfunction "2_2") (pintype "passive"))
      (node (ref "C36") (pin "N") (pinfunction "N_N") (pintype "passive"))
      (node (ref "C37") (pin "2") (pinfunction "2_2") (pintype "passive"))
      (node (ref "C38") (pin "2") (pinfunction "2_2") (pintype "passive"))
      (node (ref "C39") (pin "2") (pinfunction "2_2") (pintype "passive"))
      (node (ref "C4") (pin "N") (pinfunction "N_N") (pintype "passive"))
      (node (ref "C40") (pin "N") (pinfunction "N_N") (pintype "passive"))
      (node (ref "C41") (pin "N") (pinfunction "N_N") (pintype "passive"))
      (node (ref "C42") (pin "N") (pinfunction "N_N") (pintype "passive"))
      (node (ref "C5") (pin "2") (pinfunction "2_2") (pintype "passive"))
      (node (ref "C6") (pin "N") (pinfunction "N_N") (pintype "passive"))
      (node (ref "C7") (pin "2") (pinfunction "2_2") (pintype "passive"))
      (node (ref "C8") (pin "N") (pinfunction "N_N") (pintype "passive"))
      (node (ref "C9") (pin "2") (pinfunction "2_2") (pintype "passive"))
      (node (ref "COMP0") (pin "4") (pinfunction "VCC_4") (pintype "bidirectional"))
      (node (ref "COMP1") (pin "4") (pinfunction "VCC_4") (pintype "bidirectional"))
      (node (ref "COMP2") (pin "4") (pinfunction "VCC_4") (pintype "bidirectional"))
      (node (ref "COMP3") (pin "4") (pinfunction "VCC_4") (pintype "bidirectional"))
      (node (ref "COMP4") (pin "4") (pinfunction "VCC_4") (pintype "bidirectional"))
      (node (ref "COMP5") (pin "4") (pinfunction "VCC_4") (pintype "bidirectional"))
      (node (ref "COUNT0") (pin "3") (pinfunction "A0_3") (pintype "bidirectional"))
      (node (ref "COUNT0") (pin "8") (pinfunction "VDD_8") (pintype "bidirectional"))
      (node (ref "COUNT1") (pin "3") (pinfunction "A0_3") (pintype "bidirectional"))
      (node (ref "COUNT1") (pin "8") (pinfunction "VDD_8") (pintype "bidirectional"))
      (node (ref "COUNT2") (pin "3") (pinfunction "A0_3") (pintype "bidirectional"))
      (node (ref "COUNT2") (pin "8") (pinfunction "VDD_8") (pintype "bidirectional"))
      (node (ref "COUNT3") (pin "3") (pinfunction "A0_3") (pintype "bidirectional"))
      (node (ref "COUNT3") (pin "8") (pinfunction "VDD_8") (pintype "bidirectional"))
      (node (ref "COUNT4") (pin "8") (pinfunction "VDD_8") (pintype "bidirectional"))
      (node (ref "COUNT5") (pin "8") (pinfunction "VDD_8") (pintype "bidirectional"))
      (node (ref "COUNT6") (pin "8") (pinfunction "VDD_8") (pintype "bidirectional"))
      (node (ref "COUNT7") (pin "8") (pinfunction "VDD_8") (pintype "bidirectional"))
      (node (ref "DAC0") (pin "12") (pinfunction "VDD_12") (pintype "bidirectional"))
      (node (ref "DAC0") (pin "13") (pinfunction "REF3_13") (pintype "bidirectional"))
      (node (ref "DAC0") (pin "14") (pinfunction "REF2_14") (pintype "bidirectional"))
      (node (ref "DAC0") (pin "3") (pinfunction "REF1_3") (pintype "bidirectional"))
      (node (ref "DAC0") (pin "4") (pinfunction "REF0_4") (pintype "bidirectional"))
      (node (ref "DAC1") (pin "12") (pinfunction "VDD_12") (pintype "bidirectional"))
      (node (ref "DAC1") (pin "13") (pinfunction "REF3_13") (pintype "bidirectional"))
      (node (ref "DAC1") (pin "14") (pinfunction "REF2_14") (pintype "bidirectional"))
      (node (ref "DAC1") (pin "3") (pinfunction "REF1_3") (pintype "bidirectional"))
      (node (ref "DAC1") (pin "4") (pinfunction "REF0_4") (pintype "bidirectional"))
      (node (ref "DAC1") (pin "9") (pinfunction "AD0_9") (pintype "bidirectional"))
      (node (ref "ENCODER") (pin "4") (pinfunction "4_4") (pintype "passive"))
      (node (ref "L2") (pin "2") (pinfunction "2_2") (pintype "passive"))
      (node (ref "MULT0") (pin "16") (pinfunction "VDD_16") (pintype "bidirectional"))
      (node (ref "POW0") (pin "4") (pinfunction "SHDN_4") (pintype "bidirectional"))
      (node (ref "POW0") (pin "5") (pinfunction "VCC_5") (pintype "bidirectional"))
      (node (ref "POW1") (pin "1") (pinfunction "VIN_1") (pintype "bidirectional"))
      (node (ref "POWER") (pin "1") (pinfunction "1_1") (pintype "passive"))
      (node (ref "R1") (pin "1") (pinfunction "1_1") (pintype "passive"))
      (node (ref "RTD0") (pin "8") (pinfunction "VDD_8") (pintype "bidirectional"))
      (node (ref "RTD2") (pin "3") (pinfunction "3_3") (pintype "passive"))
      (node (ref "RTD2") (pin "4") (pinfunction "4_4") (pintype "passive"))
      (node (ref "U1") (pin "7") (pinfunction "VPOS_7") (pintype "bidirectional"))
    )
    (net (code "2") (name "+12V") (class "Default")
      (node (ref "POW1") (pin "6") (pinfunction "+VO_6") (pintype "bidirectional"))
      (node (ref "PREAMP") (pin "1") (pinfunction "1_1") (pintype "passive"))
    )
    (net (code "3") (name "-12V") (class "Default")
      (node (ref "POW1") (pin "4") (pinfunction "-VO_4") (pintype "bidirectional"))
    )
    (net (code "4") (name "/AND0") (class "Default")
      (node (ref "COMP2") (pin "3") (pinfunction "INA+_3") (pintype "bidirectional"))
      (node (ref "R3") (pin "1") (pinfunction "1_1") (pintype "passive"))
      (node (ref "R4") (pin "1") (pinfunction "1_1") (pintype "passive"))
    )
    (net (code "5") (name "/AND1") (class "Default")
      (node (ref "COMP2") (pin "5") (pinfunction "INB+_5") (pintype "bidirectional"))
      (node (ref "R5") (pin "2") (pinfunction "2_2") (pintype "passive"))
      (node (ref "R6") (pin "2") (pinfunction "2_2") (pintype "passive"))
    )
    (net (code "6") (name "/AND2") (class "Default")
      (node (ref "COMP2") (pin "10") (pinfunction "INC+_10") (pintype "bidirectional"))
      (node (ref "R2") (pin "1") (pinfunction "1_1") (pintype "passive"))
      (node (ref "R7") (pin "1") (pinfunction "1_1") (pintype "passive"))
    )
    (net (code "7") (name "/AND3") (class "Default")
      (node (ref "COMP2") (pin "12") (pinfunction "IND+_12") (pintype "bidirectional"))
      (node (ref "R14") (pin "2") (pinfunction "2_2") (pintype "passive"))
      (node (ref "R8") (pin "2") (pinfunction "2_2") (pintype "passive"))
    )
    (net (code "8") (name "/AND4") (class "Default")
      (node (ref "COMP5") (pin "3") (pinfunction "INA+_3") (pintype "bidirectional"))
      (node (ref "R10") (pin "1") (pinfunction "1_1") (pintype "passive"))
      (node (ref "R17") (pin "1") (pinfunction "1_1") (pintype "passive"))
    )
    (net (code "9") (name "/AND5") (class "Default")
      (node (ref "COMP5") (pin "5") (pinfunction "INB+_5") (pintype "bidirectional"))
      (node (ref "R15") (pin "2") (pinfunction "2_2") (pintype "passive"))
      (node (ref "R16") (pin "2") (pinfunction "2_2") (pintype "passive"))
    )
    (net (code "10") (name "/AND6") (class "Default")
      (node (ref "COMP5") (pin "12") (pinfunction "IND+_12") (pintype "bidirectional"))
      (node (ref "R18") (pin "1") (pinfunction "1_1") (pintype "passive"))
      (node (ref "R19") (pin "1") (pinfunction "1_1") (pintype "passive"))
    )
    (net (code "11") (name "/BIN0") (class "Default")
      (node (ref "COMP2") (pin "1") (pinfunction "OUTA_1") (pintype "bidirectional"))
      (node (ref "COUNT0") (pin "1") (pinfunction "OSCI_1") (pintype "bidirectional"))
    )
    (net (code "12") (name "/BIN1") (class "Default")
      (node (ref "COMP2") (pin "7") (pinfunction "OUTB_7") (pintype "bidirectional"))
      (node (ref "COUNT1") (pin "1") (pinfunction "OSCI_1") (pintype "bidirectional"))
    )
    (net (code "13") (name "/BIN2") (class "Default")
      (node (ref "COMP2") (pin "8") (pinfunction "OUTC_8") (pintype "bidirectional"))
      (node (ref "COUNT2") (pin "1") (pinfunction "OSCI_1") (pintype "bidirectional"))
    )
    (net (code "14") (name "/BIN3") (class "Default")
      (node (ref "COMP2") (pin "14") (pinfunction "OUTD_14") (pintype "bidirectional"))
      (node (ref "COUNT3") (pin "1") (pinfunction "OSCI_1") (pintype "bidirectional"))
    )
    (net (code "15") (name "/BIN4") (class "Default")
      (node (ref "COMP5") (pin "1") (pinfunction "OUTA_1") (pintype "bidirectional"))
      (node (ref "COUNT4") (pin "1") (pinfunction "OSCI_1") (pintype "bidirectional"))
    )
    (net (code "16") (name "/BIN5") (class "Default")
      (node (ref "COMP5") (pin "7") (pinfunction "OUTB_7") (pintype "bidirectional"))
      (node (ref "COUNT5") (pin "1") (pinfunction "OSCI_1") (pintype "bidirectional"))
    )
    (net (code "17") (name "/BIN6") (class "Default")
      (node (ref "COMP5") (pin "14") (pinfunction "OUTD_14") (pintype "bidirectional"))
      (node (ref "COUNT6") (pin "1") (pinfunction "OSCI_1") (pintype "bidirectional"))
    )
    (net (code "18") (name "/ENCODER") (class "Default")
      (node (ref "COUNT7") (pin "1") (pinfunction "OSCI_1") (pintype "bidirectional"))
    )
    (net (code "19") (name "/LEVEL0") (class "Default")
      (node (ref "COMP0") (pin "2") (pinfunction "INA-_2") (pintype "bidirectional"))
      (node (ref "DAC0") (pin "2") (pinfunction "OUT0_2") (pintype "bidirectional"))
      (node (ref "LEVELS") (pin "1") (pinfunction "1_1") (pintype "passive"))
    )
    (net (code "20") (name "/LEVEL1") (class "Default")
      (node (ref "COMP0") (pin "5") (pinfunction "INB+_5") (pintype "bidirectional"))
      (node (ref "COMP0") (pin "9") (pinfunction "INC-_9") (pintype "bidirectional"))
      (node (ref "DAC0") (pin "1") (pinfunction "OUT1_1") (pintype "bidirectional"))
      (node (ref "LEVELS") (pin "2") (pinfunction "2_2") (pintype "passive"))
    )
    (net (code "21") (name "/LEVEL2") (class "Default")
      (node (ref "COMP0") (pin "12") (pinfunction "IND+_12") (pintype "bidirectional"))
      (node (ref "COMP1") (pin "2") (pinfunction "INA-_2") (pintype "bidirectional"))
      (node (ref "DAC0") (pin "16") (pinfunction "OUT2_16") (pintype "bidirectional"))
      (node (ref "LEVELS") (pin "3") (pinfunction "3_3") (pintype "passive"))
    )
    (net (code "22") (name "/LEVEL3") (class "Default")
      (node (ref "COMP1") (pin "5") (pinfunction "INB+_5") (pintype "bidirectional"))
      (node (ref "COMP1") (pin "9") (pinfunction "INC-_9") (pintype "bidirectional"))
      (node (ref "DAC0") (pin "15") (pinfunction "OUT3_15") (pintype "bidirectional"))
      (node (ref "LEVELS") (pin "4") (pinfunction "4_4") (pintype "passive"))
    )
    (net (code "23") (name "/LEVEL4") (class "Default")
      (node (ref "COMP1") (pin "12") (pinfunction "IND+_12") (pintype "bidirectional"))
      (node (ref "COMP3") (pin "2") (pinfunction "INA-_2") (pintype "bidirectional"))
      (node (ref "DAC1") (pin "2") (pinfunction "OUT0_2") (pintype "bidirectional"))
      (node (ref "LEVELS") (pin "5") (pinfunction "5_5") (pintype "passive"))
    )
    (net (code "24") (name "/LEVEL5") (class "Default")
      (node (ref "COMP3") (pin "5") (pinfunction "INB+_5") (pintype "bidirectional"))
      (node (ref "COMP3") (pin "9") (pinfunction "INC-_9") (pintype "bidirectional"))
      (node (ref "DAC1") (pin "1") (pinfunction "OUT1_1") (pintype "bidirectional"))
      (node (ref "LEVELS") (pin "6") (pinfunction "6_6") (pintype "passive"))
    )
    (net (code "25") (name "/LEVEL6") (class "Default")
      (node (ref "COMP3") (pin "12") (pinfunction "IND+_12") (pintype "bidirectional"))
      (node (ref "COMP4") (pin "2") (pinfunction "INA-_2") (pintype "bidirectional"))
      (node (ref "DAC1") (pin "16") (pinfunction "OUT2_16") (pintype "bidirectional"))
      (node (ref "LEVELS") (pin "7") (pinfunction "7_7") (pintype "passive"))
    )
    (net (code "26") (name "/LEVEL7") (class "Default")
      (node (ref "COMP4") (pin "5") (pinfunction "INB+_5") (pintype "bidirectional"))
      (node (ref "DAC1") (pin "15") (pinfunction "OUT3_15") (pintype "bidirectional"))
      (node (ref "LEVELS") (pin "8") (pinfunction "8_8") (pintype "passive"))
    )
    (net (code "27") (name "/OUTA") (class "Default")
      (node (ref "ENCODER") (pin "3") (pinfunction "3_3") (pintype "passive"))
    )
    (net (code "28") (name "/OUTB") (class "Default")
      (node (ref "ENCODER") (pin "2") (pinfunction "2_2") (pintype "passive"))
    )
    (net (code "29") (name "/RESET") (class "Default")
      (node (ref "MULT0") (pin "3") (pinfunction "RESET_3") (pintype "bidirectional"))
    )
    (net (code "30") (name "/SC0") (class "Default")
      (node (ref "COUNT0") (pin "6") (pinfunction "SCL_6") (pintype "bidirectional"))
      (node (ref "COUNT4") (pin "6") (pinfunction "SCL_6") (pintype "bidirectional"))
      (node (ref "MULT0") (pin "5") (pinfunction "SC0_5") (pintype "bidirectional"))
    )
    (net (code "31") (name "/SC1") (class "Default")
      (node (ref "COUNT1") (pin "6") (pinfunction "SCL_6") (pintype "bidirectional"))
      (node (ref "COUNT5") (pin "6") (pinfunction "SCL_6") (pintype "bidirectional"))
      (node (ref "MULT0") (pin "7") (pinfunction "SC1_7") (pintype "bidirectional"))
    )
    (net (code "32") (name "/SC2") (class "Default")
      (node (ref "COUNT2") (pin "6") (pinfunction "SCL_6") (pintype "bidirectional"))
      (node (ref "COUNT6") (pin "6") (pinfunction "SCL_6") (pintype "bidirectional"))
      (node (ref "MULT0") (pin "10") (pinfunction "SC2_10") (pintype "bidirectional"))
    )
    (net (code "33") (name "/SC3") (class "Default")
      (node (ref "COUNT3") (pin "6") (pinfunction "SCL_6") (pintype "bidirectional"))
      (node (ref "COUNT7") (pin "6") (pinfunction "SCL_6") (pintype "bidirectional"))
      (node (ref "MULT0") (pin "12") (pinfunction "SC3_12") (pintype "bidirectional"))
    )
    (net (code "34") (name "/SCL") (class "Default")
      (node (ref "DAC0") (pin "7") (pinfunction "SCL_7") (pintype "bidirectional"))
      (node (ref "DAC1") (pin "7") (pinfunction "SCL_7") (pintype "bidirectional"))
      (node (ref "I2C") (pin "1") (pinfunction "1_1") (pintype "passive"))
      (node (ref "MULT0") (pin "14") (pinfunction "SCL_14") (pintype "bidirectional"))
      (node (ref "RTD0") (pin "2") (pinfunction "SCL_2") (pintype "bidirectional"))
      (node (ref "RTD1") (pin "2") (pinfunction "2_2") (pintype "passive"))
    )
    (net (code "35") (name "/SD0") (class "Default")
      (node (ref "COUNT0") (pin "5") (pinfunction "SDA_5") (pintype "bidirectional"))
      (node (ref "COUNT4") (pin "5") (pinfunction "SDA_5") (pintype "bidirectional"))
      (node (ref "MULT0") (pin "4") (pinfunction "SD0_4") (pintype "bidirectional"))
    )
    (net (code "36") (name "/SD1") (class "Default")
      (node (ref "COUNT1") (pin "5") (pinfunction "SDA_5") (pintype "bidirectional"))
      (node (ref "COUNT5") (pin "5") (pinfunction "SDA_5") (pintype "bidirectional"))
      (node (ref "MULT0") (pin "6") (pinfunction "SD1_6") (pintype "bidirectional"))
    )
    (net (code "37") (name "/SD2") (class "Default")
      (node (ref "COUNT2") (pin "5") (pinfunction "SDA_5") (pintype "bidirectional"))
      (node (ref "COUNT6") (pin "5") (pinfunction "SDA_5") (pintype "bidirectional"))
      (node (ref "MULT0") (pin "9") (pinfunction "SD2_9") (pintype "bidirectional"))
    )
    (net (code "38") (name "/SD3") (class "Default")
      (node (ref "COUNT3") (pin "5") (pinfunction "SDA_5") (pintype "bidirectional"))
      (node (ref "COUNT7") (pin "5") (pinfunction "SDA_5") (pintype "bidirectional"))
      (node (ref "MULT0") (pin "11") (pinfunction "SD3_11") (pintype "bidirectional"))
    )
    (net (code "39") (name "/SDA") (class "Default")
      (node (ref "DAC0") (pin "8") (pinfunction "SDA_8") (pintype "bidirectional"))
      (node (ref "DAC1") (pin "8") (pinfunction "SDA_8") (pintype "bidirectional"))
      (node (ref "I2C") (pin "2") (pinfunction "2_2") (pintype "passive"))
      (node (ref "MULT0") (pin "15") (pinfunction "SDA_15") (pintype "bidirectional"))
      (node (ref "RTD0") (pin "1") (pinfunction "SDA_1") (pintype "bidirectional"))
      (node (ref "RTD1") (pin "1") (pinfunction "1_1") (pintype "passive"))
    )
    (net (code "40") (name "/SIGNAL") (class "Default")
      (node (ref "COMP0") (pin "10") (pinfunction "INC+_10") (pintype "bidirectional"))
      (node (ref "COMP0") (pin "13") (pinfunction "IND-_13") (pintype "bidirectional"))
      (node (ref "COMP0") (pin "3") (pinfunction "INA+_3") (pintype "bidirectional"))
      (node (ref "COMP0") (pin "6") (pinfunction "INB-_6") (pintype "bidirectional"))
      (node (ref "COMP1") (pin "10") (pinfunction "INC+_10") (pintype "bidirectional"))
      (node (ref "COMP1") (pin "13") (pinfunction "IND-_13") (pintype "bidirectional"))
      (node (ref "COMP1") (pin "3") (pinfunction "INA+_3") (pintype "bidirectional"))
      (node (ref "COMP1") (pin "6") (pinfunction "INB-_6") (pintype "bidirectional"))
      (node (ref "COMP3") (pin "10") (pinfunction "INC+_10") (pintype "bidirectional"))
      (node (ref "COMP3") (pin "13") (pinfunction "IND-_13") (pintype "bidirectional"))
      (node (ref "COMP3") (pin "3") (pinfunction "INA+_3") (pintype "bidirectional"))
      (node (ref "COMP3") (pin "6") (pinfunction "INB-_6") (pintype "bidirectional"))
      (node (ref "COMP4") (pin "3") (pinfunction "INA+_3") (pintype "bidirectional"))
      (node (ref "COMP4") (pin "6") (pinfunction "INB-_6") (pintype "bidirectional"))
      (node (ref "SIGNAL") (pin "1") (pinfunction "1_1") (pintype "passive"))
    )
    (net (code "41") (name "30V") (class "Default")
      (node (ref "BIAS") (pin "1") (pinfunction "1_1") (pintype "passive"))
      (node (ref "C16") (pin "2") (pinfunction "2_2") (pintype "passive"))
      (node (ref "D1") (pin "C") (pinfunction "C_C") (pintype "passive"))
      (node (ref "R22") (pin "2") (pinfunction "2_2") (pintype "passive"))
    )
    (net (code "42") (name "GND") (class "Default")
      (node (ref "52.3") (pin "2") (pinfunction "2_2") (pintype "passive"))
      (node (ref "BIAS") (pin "2") (pinfunction "MNT_1_2") (pintype "passive"))
      (node (ref "BIAS") (pin "3") (pinfunction "MNT_2_3") (pintype "passive"))
      (node (ref "BIAS") (pin "4") (pinfunction "MNT_3_4") (pintype "passive"))
      (node (ref "BIAS") (pin "5") (pinfunction "MNT_4_5") (pintype "passive"))
      (node (ref "C1") (pin "1") (pinfunction "1_1") (pintype "passive"))
      (node (ref "C10") (pin "1") (pinfunction "1_1") (pintype "passive"))
      (node (ref "C11") (pin "P") (pinfunction "P_P") (pintype "passive"))
      (node (ref "C12") (pin "P") (pinfunction "P_P") (pintype "passive"))
      (node (ref "C13") (pin "1") (pinfunction "1_1") (pintype "passive"))
      (node (ref "C14") (pin "1") (pinfunction "1_1") (pintype "passive"))
      (node (ref "C15") (pin "1") (pinfunction "1_1") (pintype "passive"))
      (node (ref "C16") (pin "1") (pinfunction "1_1") (pintype "passive"))
      (node (ref "C17") (pin "1") (pinfunction "1_1") (pintype "passive"))
      (node (ref "C18") (pin "P") (pinfunction "P_P") (pintype "passive"))
      (node (ref "C19") (pin "P") (pinfunction "P_P") (pintype "passive"))
      (node (ref "C2") (pin "P") (pinfunction "P_P") (pintype "passive"))
      (node (ref "C20") (pin "P") (pinfunction "P_P") (pintype "passive"))
      (node (ref "C21") (pin "1") (pinfunction "1_1") (pintype "passive"))
      (node (ref "C22") (pin "1") (pinfunction "1_1") (pintype "passive"))
      (node (ref "C23") (pin "1") (pinfunction "1_1") (pintype "passive"))
      (node (ref "C24") (pin "P") (pinfunction "P_P") (pintype "passive"))
      (node (ref "C25") (pin "1") (pinfunction "1_1") (pintype "passive"))
      (node (ref "C26") (pin "P") (pinfunction "P_P") (pintype "passive"))
      (node (ref "C27") (pin "1") (pinfunction "1_1") (pintype "passive"))
      (node (ref "C28") (pin "P") (pinfunction "P_P") (pintype "passive"))
      (node (ref "C29") (pin "1") (pinfunction "1_1") (pintype "passive"))
      (node (ref "C3") (pin "1") (pinfunction "1_1") (pintype "passive"))
      (node (ref "C30") (pin "P") (pinfunction "P_P") (pintype "passive"))
      (node (ref "C31") (pin "1") (pinfunction "1_1") (pintype "passive"))
      (node (ref "C32") (pin "P") (pinfunction "P_P") (pintype "passive"))
      (node (ref "C33") (pin "1") (pinfunction "1_1") (pintype "passive"))
      (node (ref "C34") (pin "P") (pinfunction "P_P") (pintype "passive"))
      (node (ref "C35") (pin "1") (pinfunction "1_1") (pintype "passive"))
      (node (ref "C36") (pin "P") (pinfunction "P_P") (pintype "passive"))
      (node (ref "C37") (pin "1") (pinfunction "1_1") (pintype "passive"))
      (node (ref "C38") (pin "1") (pinfunction "1_1") (pintype "passive"))
      (node (ref "C39") (pin "1") (pinfunction "1_1") (pintype "passive"))
      (node (ref "C4") (pin "P") (pinfunction "P_P") (pintype "passive"))
      (node (ref "C40") (pin "P") (pinfunction "P_P") (pintype "passive"))
      (node (ref "C41") (pin "P") (pinfunction "P_P") (pintype "passive"))
      (node (ref "C42") (pin "P") (pinfunction "P_P") (pintype "passive"))
      (node (ref "C44") (pin "2") (pinfunction "2_2") (pintype "passive"))
      (node (ref "C5") (pin "1") (pinfunction "1_1") (pintype "passive"))
      (node (ref "C6") (pin "P") (pinfunction "P_P") (pintype "passive"))
      (node (ref "C7") (pin "1") (pinfunction "1_1") (pintype "passive"))
      (node (ref "C8") (pin "P") (pinfunction "P_P") (pintype "passive"))
      (node (ref "C9") (pin "1") (pinfunction "1_1") (pintype "passive"))
      (node (ref "COMP0") (pin "11") (pinfunction "GND_11") (pintype "bidirectional"))
      (node (ref "COMP1") (pin "11") (pinfunction "GND_11") (pintype "bidirectional"))
      (node (ref "COMP2") (pin "11") (pinfunction "GND_11") (pintype "bidirectional"))
      (node (ref "COMP3") (pin "11") (pinfunction "GND_11") (pintype "bidirectional"))
      (node (ref "COMP5") (pin "11") (pinfunction "GND_11") (pintype "bidirectional"))
      (node (ref "COUNT0") (pin "4") (pinfunction "VSS_4") (pintype "bidirectional"))
      (node (ref "COUNT1") (pin "4") (pinfunction "VSS_4") (pintype "bidirectional"))
      (node (ref "COUNT2") (pin "4") (pinfunction "VSS_4") (pintype "bidirectional"))
      (node (ref "COUNT3") (pin "4") (pinfunction "VSS_4") (pintype "bidirectional"))
      (node (ref "COUNT4") (pin "3") (pinfunction "A0_3") (pintype "bidirectional"))
      (node (ref "COUNT4") (pin "4") (pinfunction "VSS_4") (pintype "bidirectional"))
      (node (ref "COUNT5") (pin "3") (pinfunction "A0_3") (pintype "bidirectional"))
      (node (ref "COUNT5") (pin "4") (pinfunction "VSS_4") (pintype "bidirectional"))
      (node (ref "COUNT6") (pin "3") (pinfunction "A0_3") (pintype "bidirectional"))
      (node (ref "COUNT6") (pin "4") (pinfunction "VSS_4") (pintype "bidirectional"))
      (node (ref "COUNT7") (pin "3") (pinfunction "A0_3") (pintype "bidirectional"))
      (node (ref "COUNT7") (pin "4") (pinfunction "VSS_4") (pintype "bidirectional"))
      (node (ref "DAC0") (pin "10") (pinfunction "AD1_10") (pintype "bidirectional"))
      (node (ref "DAC0") (pin "11") (pinfunction "AD2_11") (pintype "bidirectional"))
      (node (ref "DAC0") (pin "5") (pinfunction "AGND_5") (pintype "bidirectional"))
      (node (ref "DAC0") (pin "6") (pinfunction "DGND_6") (pintype "bidirectional"))
      (node (ref "DAC0") (pin "9") (pinfunction "AD0_9") (pintype "bidirectional"))
      (node (ref "DAC1") (pin "10") (pinfunction "AD1_10") (pintype "bidirectional"))
      (node (ref "DAC1") (pin "11") (pinfunction "AD2_11") (pintype "bidirectional"))
      (node (ref "DAC1") (pin "5") (pinfunction "AGND_5") (pintype "bidirectional"))
      (node (ref "DAC1") (pin "6") (pinfunction "DGND_6") (pintype "bidirectional"))
      (node (ref "ENCODER") (pin "1") (pinfunction "1_1") (pintype "passive"))
      (node (ref "MULT0") (pin "1") (pinfunction "A0_1") (pintype "bidirectional"))
      (node (ref "MULT0") (pin "13") (pinfunction "A2_13") (pintype "bidirectional"))
      (node (ref "MULT0") (pin "2") (pinfunction "A1_2") (pintype "bidirectional"))
      (node (ref "MULT0") (pin "8") (pinfunction "VSS_8") (pintype "bidirectional"))
      (node (ref "POW0") (pin "1") (pinfunction "PGND_1") (pintype "bidirectional"))
      (node (ref "POW0") (pin "2") (pinfunction "GND_2") (pintype "bidirectional"))
      (node (ref "POW1") (pin "2") (pinfunction "GND_2") (pintype "bidirectional"))
      (node (ref "POW1") (pin "5") (pinfunction "0V_5") (pintype "bidirectional"))
      (node (ref "PREAMP") (pin "2") (pinfunction "2_2") (pintype "passive"))
      (node (ref "R11") (pin "2") (pinfunction "2_2") (pintype "passive"))
      (node (ref "R23") (pin "1") (pinfunction "1_1") (pintype "passive"))
      (node (ref "R9") (pin "2") (pinfunction "2_2") (pintype "passive"))
      (node (ref "RTD0") (pin "4") (pinfunction "GND_4") (pintype "bidirectional"))
      (node (ref "RTD0") (pin "5") (pinfunction "AD2_5") (pintype "bidirectional"))
      (node (ref "RTD0") (pin "6") (pinfunction "AD1_6") (pintype "bidirectional"))
      (node (ref "RTD0") (pin "7") (pinfunction "AD0_7") (pintype "bidirectional"))
      (node (ref "RTD1") (pin "4") (pinfunction "4_4") (pintype "passive"))
      (node (ref "RTD2") (pin "2") (pinfunction "2_2") (pintype "passive"))
      (node (ref "SIGNAL") (pin "2") (pinfunction "MNT_1_2") (pintype "passive"))
      (node (ref "SIGNAL") (pin "3") (pinfunction "MNT_2_3") (pintype "passive"))
      (node (ref "SIGNAL") (pin "4") (pinfunction "MNT_3_4") (pintype "passive"))
      (node (ref "SIGNAL") (pin "5") (pinfunction "MNT_4_5") (pintype "passive"))
    )
    (net (code "43") (name "Net-(52.3-Pad1)") (class "Default")
      (node (ref "52.3") (pin "1") (pinfunction "1_1") (pintype "passive"))
      (node (ref "C43") (pin "1") (pinfunction "1_1") (pintype "passive"))
    )
    (net (code "44") (name "Net-(COMP0-OUTA)") (class "Default")
      (node (ref "COMP0") (pin "1") (pinfunction "OUTA_1") (pintype "bidirectional"))
      (node (ref "R3") (pin "2") (pinfunction "2_2") (pintype "passive"))
    )
    (net (code "45") (name "Net-(COMP0-OUTB)") (class "Default")
      (node (ref "COMP0") (pin "7") (pinfunction "OUTB_7") (pintype "bidirectional"))
      (node (ref "R4") (pin "2") (pinfunction "2_2") (pintype "passive"))
    )
    (net (code "46") (name "Net-(COMP0-OUTC)") (class "Default")
      (node (ref "COMP0") (pin "8") (pinfunction "OUTC_8") (pintype "bidirectional"))
      (node (ref "R6") (pin "1") (pinfunction "1_1") (pintype "passive"))
    )
    (net (code "47") (name "Net-(COMP0-OUTD)") (class "Default")
      (node (ref "COMP0") (pin "14") (pinfunction "OUTD_14") (pintype "bidirectional"))
      (node (ref "R5") (pin "1") (pinfunction "1_1") (pintype "passive"))
    )
    (net (code "48") (name "Net-(COMP1-OUTA)") (class "Default")
      (node (ref "COMP1") (pin "1") (pinfunction "OUTA_1") (pintype "bidirectional"))
      (node (ref "R2") (pin "2") (pinfunction "2_2") (pintype "passive"))
    )
    (net (code "49") (name "Net-(COMP1-OUTB)") (class "Default")
      (node (ref "COMP1") (pin "7") (pinfunction "OUTB_7") (pintype "bidirectional"))
      (node (ref "R7") (pin "2") (pinfunction "2_2") (pintype "passive"))
    )
    (net (code "50") (name "Net-(COMP1-OUTC)") (class "Default")
      (node (ref "COMP1") (pin "8") (pinfunction "OUTC_8") (pintype "bidirectional"))
      (node (ref "R14") (pin "1") (pinfunction "1_1") (pintype "passive"))
    )
    (net (code "51") (name "Net-(COMP1-OUTD)") (class "Default")
      (node (ref "COMP1") (pin "14") (pinfunction "OUTD_14") (pintype "bidirectional"))
      (node (ref "R8") (pin "1") (pinfunction "1_1") (pintype "passive"))
    )
    (net (code "52") (name "Net-(COMP2-INA-)") (class "Default")
      (node (ref "COMP2") (pin "13") (pinfunction "IND-_13") (pintype "bidirectional"))
      (node (ref "COMP2") (pin "2") (pinfunction "INA-_2") (pintype "bidirectional"))
      (node (ref "COMP2") (pin "6") (pinfunction "INB-_6") (pintype "bidirectional"))
      (node (ref "COMP2") (pin "9") (pinfunction "INC-_9") (pintype "bidirectional"))
      (node (ref "COMP5") (pin "13") (pinfunction "IND-_13") (pintype "bidirectional"))
      (node (ref "COMP5") (pin "2") (pinfunction "INA-_2") (pintype "bidirectional"))
      (node (ref "COMP5") (pin "6") (pinfunction "INB-_6") (pintype "bidirectional"))
      (node (ref "R1") (pin "2") (pinfunction "2_2") (pintype "passive"))
      (node (ref "R9") (pin "1") (pinfunction "1_1") (pintype "passive"))
    )
    (net (code "53") (name "Net-(COMP3-OUTA)") (class "Default")
      (node (ref "COMP3") (pin "1") (pinfunction "OUTA_1") (pintype "bidirectional"))
      (node (ref "R10") (pin "2") (pinfunction "2_2") (pintype "passive"))
    )
    (net (code "54") (name "Net-(COMP3-OUTB)") (class "Default")
      (node (ref "COMP3") (pin "7") (pinfunction "OUTB_7") (pintype "bidirectional"))
      (node (ref "R17") (pin "2") (pinfunction "2_2") (pintype "passive"))
    )
    (net (code "55") (name "Net-(COMP3-OUTC)") (class "Default")
      (node (ref "COMP3") (pin "8") (pinfunction "OUTC_8") (pintype "bidirectional"))
      (node (ref "R16") (pin "1") (pinfunction "1_1") (pintype "passive"))
    )
    (net (code "56") (name "Net-(COMP3-OUTD)") (class "Default")
      (node (ref "COMP3") (pin "14") (pinfunction "OUTD_14") (pintype "bidirectional"))
      (node (ref "R15") (pin "1") (pinfunction "1_1") (pintype "passive"))
    )
    (net (code "57") (name "Net-(COMP4-OUTA)") (class "Default")
      (node (ref "COMP4") (pin "1") (pinfunction "OUTA_1") (pintype "bidirectional"))
      (node (ref "R18") (pin "2") (pinfunction "2_2") (pintype "passive"))
    )
    (net (code "58") (name "Net-(COMP4-OUTB)") (class "Default")
      (node (ref "COMP4") (pin "7") (pinfunction "OUTB_7") (pintype "bidirectional"))
      (node (ref "R19") (pin "2") (pinfunction "2_2") (pintype "passive"))
    )
    (net (code "59") (name "Net-(POW0-FB)") (class "Default")
      (node (ref "POW0") (pin "3") (pinfunction "FB_3") (pintype "bidirectional"))
      (node (ref "R22") (pin "1") (pinfunction "1_1") (pintype "passive"))
      (node (ref "R23") (pin "2") (pinfunction "2_2") (pintype "passive"))
    )
    (net (code "60") (name "Net-(POW0-LX)") (class "Default")
      (node (ref "D1") (pin "A") (pinfunction "A_A") (pintype "passive"))
      (node (ref "L2") (pin "1") (pinfunction "1_1") (pintype "passive"))
      (node (ref "POW0") (pin "6") (pinfunction "LX_6") (pintype "bidirectional"))
    )
    (net (code "61") (name "Net-(POWER-Pad2)") (class "Default")
      (node (ref "POWER") (pin "2") (pinfunction "2_2") (pintype "passive"))
      (node (ref "R11") (pin "1") (pinfunction "1_1") (pintype "passive"))
    )
    (net (code "62") (name "Net-(U1-INHI)") (class "Default")
      (node (ref "C43") (pin "2") (pinfunction "2_2") (pintype "passive"))
      (node (ref "U1") (pin "1") (pinfunction "INHI_1") (pintype "bidirectional"))
    )
    (net (code "63") (name "Net-(U1-INLO)") (class "Default")
      (node (ref "C44") (pin "1") (pinfunction "1_1") (pintype "passive"))
      (node (ref "U1") (pin "8") (pinfunction "INLO_8") (pintype "bidirectional"))
    )
    (net (code "64") (name "unconnected-(COMP4-GND-Pad11)") (class "Default")
      (node (ref "COMP4") (pin "11") (pinfunction "GND_11") (pintype "bidirectional"))
    )
    (net (code "65") (name "unconnected-(COMP4-INC+-Pad10)") (class "Default")
      (node (ref "COMP4") (pin "10") (pinfunction "INC+_10") (pintype "bidirectional"))
    )
    (net (code "66") (name "unconnected-(COMP4-INC--Pad9)") (class "Default")
      (node (ref "COMP4") (pin "9") (pinfunction "INC-_9") (pintype "bidirectional"))
    )
    (net (code "67") (name "unconnected-(COMP4-IND+-Pad12)") (class "Default")
      (node (ref "COMP4") (pin "12") (pinfunction "IND+_12") (pintype "bidirectional"))
    )
    (net (code "68") (name "unconnected-(COMP4-IND--Pad13)") (class "Default")
      (node (ref "COMP4") (pin "13") (pinfunction "IND-_13") (pintype "bidirectional"))
    )
    (net (code "69") (name "unconnected-(COMP4-OUTC-Pad8)") (class "Default")
      (node (ref "COMP4") (pin "8") (pinfunction "OUTC_8") (pintype "bidirectional"))
    )
    (net (code "70") (name "unconnected-(COMP4-OUTD-Pad14)") (class "Default")
      (node (ref "COMP4") (pin "14") (pinfunction "OUTD_14") (pintype "bidirectional"))
    )
    (net (code "71") (name "unconnected-(COMP5-INC+-Pad10)") (class "Default")
      (node (ref "COMP5") (pin "10") (pinfunction "INC+_10") (pintype "bidirectional"))
    )
    (net (code "72") (name "unconnected-(COMP5-INC--Pad9)") (class "Default")
      (node (ref "COMP5") (pin "9") (pinfunction "INC-_9") (pintype "bidirectional"))
    )
    (net (code "73") (name "unconnected-(COMP5-OUTC-Pad8)") (class "Default")
      (node (ref "COMP5") (pin "8") (pinfunction "OUTC_8") (pintype "bidirectional"))
    )
    (net (code "74") (name "unconnected-(COUNT0-INT-Pad7)") (class "Default")
      (node (ref "COUNT0") (pin "7") (pinfunction "INT_7") (pintype "bidirectional"))
    )
    (net (code "75") (name "unconnected-(COUNT0-OSCO-Pad2)") (class "Default")
      (node (ref "COUNT0") (pin "2") (pinfunction "OSCO_2") (pintype "bidirectional"))
    )
    (net (code "76") (name "unconnected-(COUNT1-INT-Pad7)") (class "Default")
      (node (ref "COUNT1") (pin "7") (pinfunction "INT_7") (pintype "bidirectional"))
    )
    (net (code "77") (name "unconnected-(COUNT1-OSCO-Pad2)") (class "Default")
      (node (ref "COUNT1") (pin "2") (pinfunction "OSCO_2") (pintype "bidirectional"))
    )
    (net (code "78") (name "unconnected-(COUNT2-INT-Pad7)") (class "Default")
      (node (ref "COUNT2") (pin "7") (pinfunction "INT_7") (pintype "bidirectional"))
    )
    (net (code "79") (name "unconnected-(COUNT2-OSCO-Pad2)") (class "Default")
      (node (ref "COUNT2") (pin "2") (pinfunction "OSCO_2") (pintype "bidirectional"))
    )
    (net (code "80") (name "unconnected-(COUNT3-INT-Pad7)") (class "Default")
      (node (ref "COUNT3") (pin "7") (pinfunction "INT_7") (pintype "bidirectional"))
    )
    (net (code "81") (name "unconnected-(COUNT3-OSCO-Pad2)") (class "Default")
      (node (ref "COUNT3") (pin "2") (pinfunction "OSCO_2") (pintype "bidirectional"))
    )
    (net (code "82") (name "unconnected-(COUNT4-INT-Pad7)") (class "Default")
      (node (ref "COUNT4") (pin "7") (pinfunction "INT_7") (pintype "bidirectional"))
    )
    (net (code "83") (name "unconnected-(COUNT4-OSCO-Pad2)") (class "Default")
      (node (ref "COUNT4") (pin "2") (pinfunction "OSCO_2") (pintype "bidirectional"))
    )
    (net (code "84") (name "unconnected-(COUNT5-INT-Pad7)") (class "Default")
      (node (ref "COUNT5") (pin "7") (pinfunction "INT_7") (pintype "bidirectional"))
    )
    (net (code "85") (name "unconnected-(COUNT5-OSCO-Pad2)") (class "Default")
      (node (ref "COUNT5") (pin "2") (pinfunction "OSCO_2") (pintype "bidirectional"))
    )
    (net (code "86") (name "unconnected-(COUNT6-INT-Pad7)") (class "Default")
      (node (ref "COUNT6") (pin "7") (pinfunction "INT_7") (pintype "bidirectional"))
    )
    (net (code "87") (name "unconnected-(COUNT6-OSCO-Pad2)") (class "Default")
      (node (ref "COUNT6") (pin "2") (pinfunction "OSCO_2") (pintype "bidirectional"))
    )
    (net (code "88") (name "unconnected-(COUNT7-INT-Pad7)") (class "Default")
      (node (ref "COUNT7") (pin "7") (pinfunction "INT_7") (pintype "bidirectional"))
    )
    (net (code "89") (name "unconnected-(COUNT7-OSCO-Pad2)") (class "Default")
      (node (ref "COUNT7") (pin "2") (pinfunction "OSCO_2") (pintype "bidirectional"))
    )
    (net (code "90") (name "unconnected-(RTD0-ALERT-Pad3)") (class "Default")
      (node (ref "RTD0") (pin "3") (pinfunction "ALERT_3") (pintype "bidirectional"))
    )
    (net (code "91") (name "unconnected-(RTD1-Pad3)") (class "Default")
      (node (ref "RTD1") (pin "3") (pinfunction "3_3") (pintype "passive"))
    )
    (net (code "92") (name "unconnected-(RTD2-Pad1)") (class "Default")
      (node (ref "RTD2") (pin "1") (pinfunction "1_1") (pintype "passive"))
    )
    (net (code "93") (name "unconnected-(U1-CLPF-Pad3)") (class "Default")
      (node (ref "U1") (pin "3") (pinfunction "CLPF_3") (pintype "bidirectional"))
    )
    (net (code "94") (name "unconnected-(U1-COMM-Pad2)") (class "Default")
      (node (ref "U1") (pin "2") (pinfunction "COMM_2") (pintype "bidirectional"))
    )
    (net (code "95") (name "unconnected-(U1-TADJ-Pad6)") (class "Default")
      (node (ref "U1") (pin "6") (pinfunction "TADJ_6") (pintype "bidirectional"))
    )
    (net (code "96") (name "unconnected-(U1-VOUT-Pad5)") (class "Default")
      (node (ref "U1") (pin "5") (pinfunction "VOUT_5") (pintype "bidirectional"))
    )
    (net (code "97") (name "unconnected-(U1-VSET-Pad4)") (class "Default")
      (node (ref "U1") (pin "4") (pinfunction "VSET_4") (pintype "bidirectional"))
    )
  )
)
